# UV_-_SERVO_CTRL.net
KiCad netlist of a schematic drawn in EAGLE
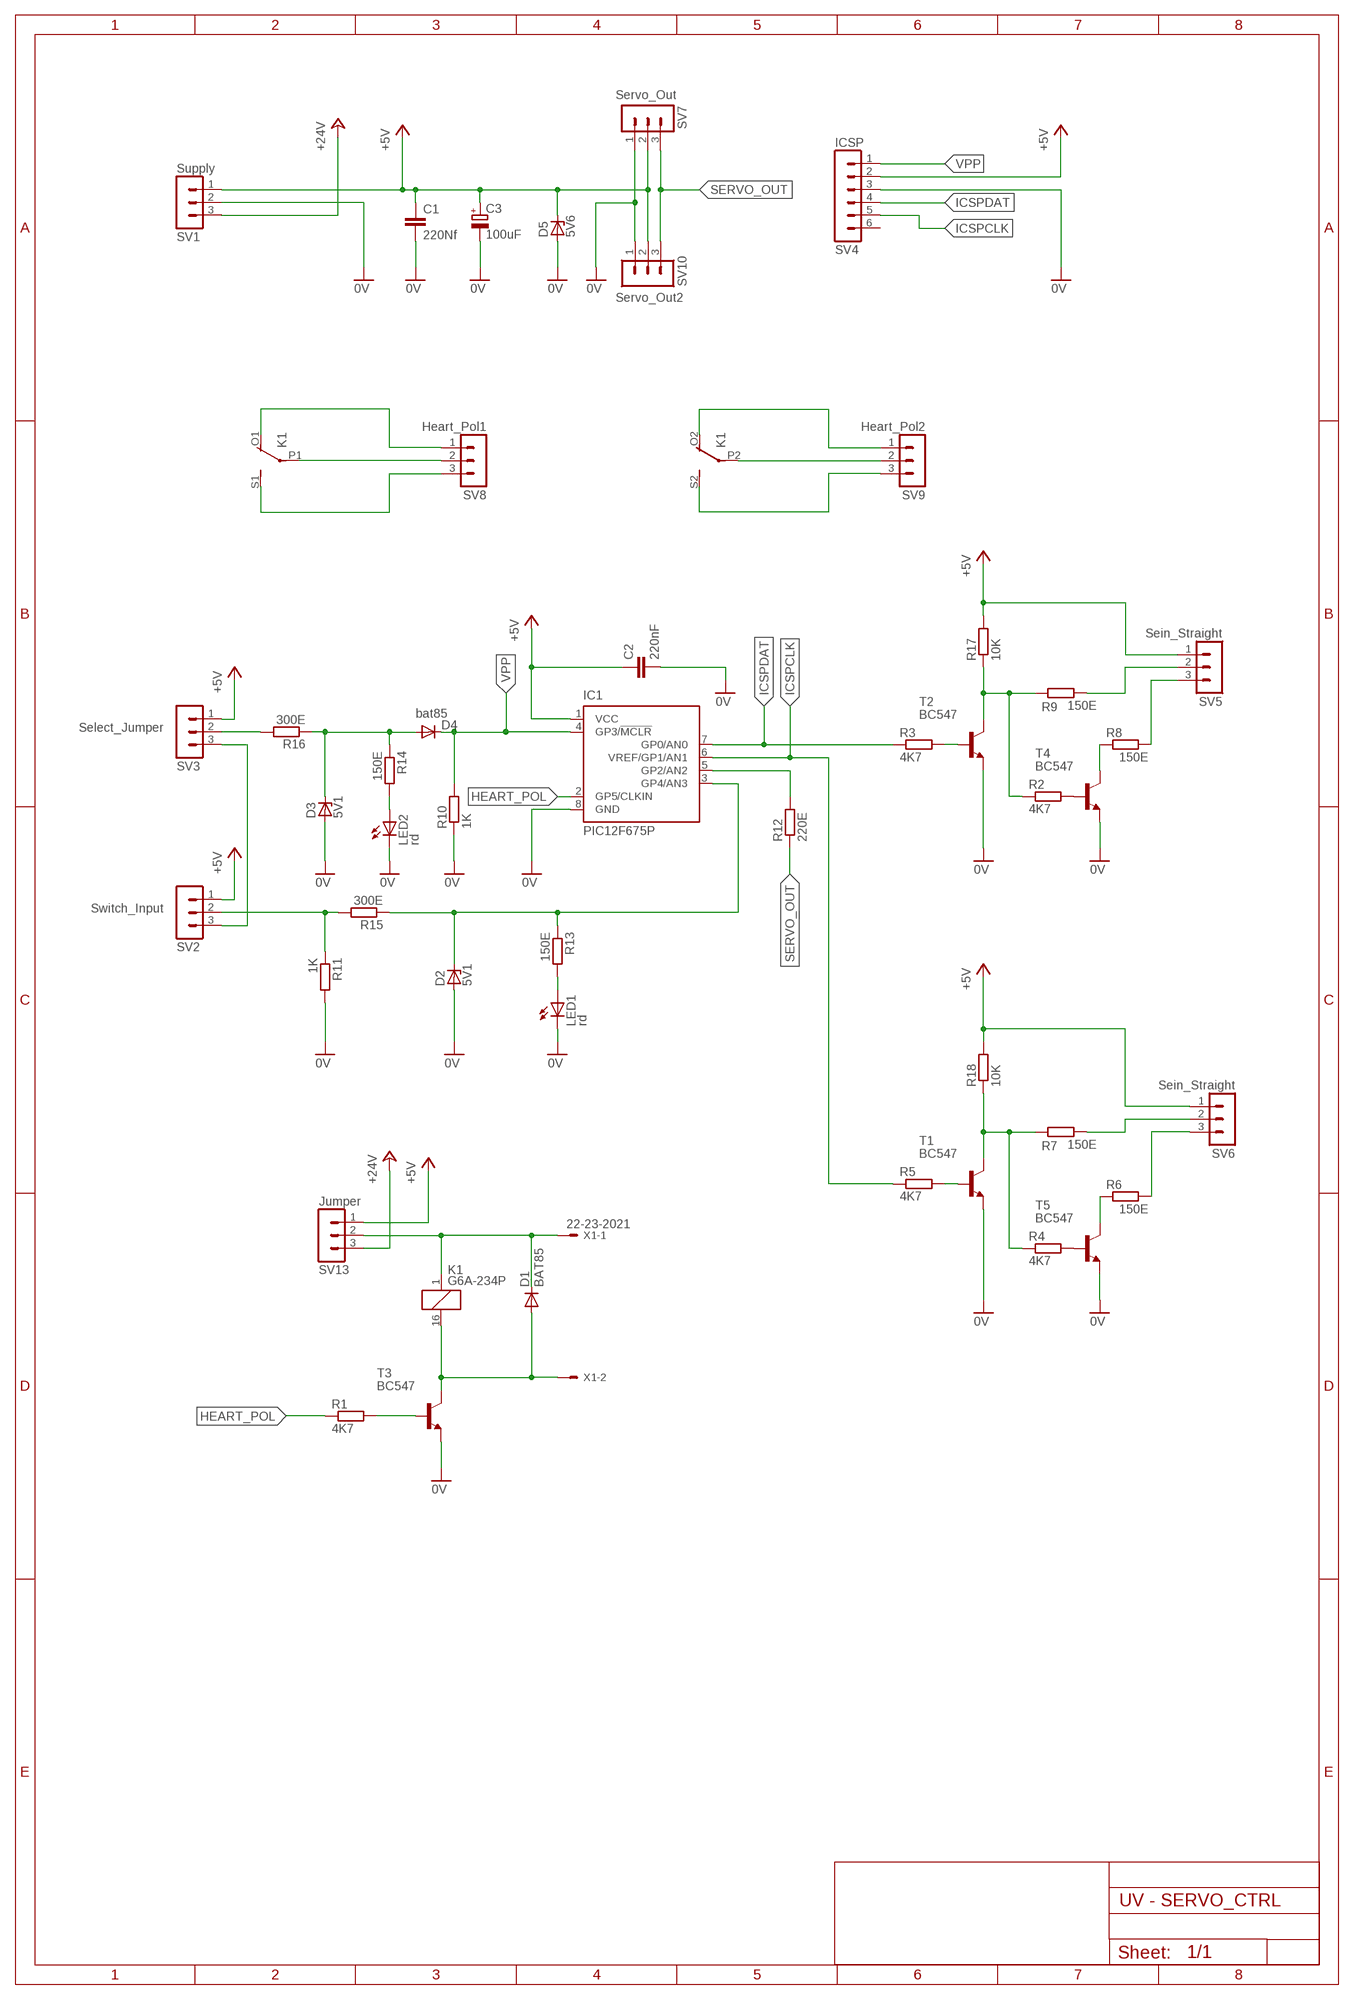
[diagram p0: schematic, sheet 1]

(export (version "E")
  (design (tool "Eeschema 10.0.6"))
  (components
    (comp (ref "C1")
      (value "220Nf")
      (footprint "eagle-import:C050-025X075")
      (fields (field (name "MPN") "MCPBSFC-1J222KA45"))
      (libsource (lib "eagle-import") (part "C-EU050-025X075"))
    )
    (comp (ref "C2")
      (value "220nF")
      (footprint "eagle-import:C050-025X075")
      (fields (field (name "MPN") "MCPBSFC-1J222KA45"))
      (libsource (lib "eagle-import") (part "C-EU050-025X075"))
    )
    (comp (ref "C3")
      (value "100uF")
      (footprint "eagle-import:E2,5-7")
      (fields (field (name "MF") "ILLINOIS CAPACITOR,INC.") (field (name "MPN") "107CKE035M"))
      (libsource (lib "eagle-import") (part "CPOL-EUE2.5-7"))
    )
    (comp (ref "D1")
      (value "BAT85")
      (footprint "eagle-import:DO34-7")
      (fields (field (name "MPN") "BAT85,113"))
      (libsource (lib "eagle-import") (part "BAT81"))
    )
    (comp (ref "D2")
      (value "5V1")
      (footprint "eagle-import:DO34Z7")
      (fields (field (name "MPN") "BZX55C5V1-TAP"))
      (libsource (lib "eagle-import") (part "ZENER-DIODEDO34-7"))
    )
    (comp (ref "D3")
      (value "5V1")
      (footprint "eagle-import:DO34Z7")
      (fields (field (name "MPN") "BZX55C5V1-TAP"))
      (libsource (lib "eagle-import") (part "ZENER-DIODEDO34-7"))
    )
    (comp (ref "D4")
      (value "bat85")
      (footprint "eagle-import:DO34-7")
      (fields (field (name "MPN") "BAT85,113"))
      (libsource (lib "eagle-import") (part "BAT81"))
    )
    (comp (ref "D5")
      (value "5V6")
      (footprint "eagle-import:C1702-15")
      (fields (field (name "MF") "FAIRCHILD SEMICONDUCTOR") (field (name "MPN") "BZX85C5V1"))
      (libsource (lib "eagle-import") (part "1N5333"))
    )
    (comp (ref "IC1")
      (value "PIC12F675P")
      (footprint "eagle-import:DIL8")
      (fields
        (field (name "MF") "MICROCHIP")
        (field (name "MPN") "PIC12F675-E/P")
        (field (name "MF_1") "MICROCHIP")
        (field (name "MPN_1") "PIC12F675-E/P")
        (field (name "OC_NEWARK") "92C4340")
      )
      (libsource (lib "eagle-import") (part "PIC12F675P"))
    )
    (comp (ref "K1")
      (value "G6A-234P")
      (footprint "eagle-import:G6A-234P")
      (fields
        (field (name "MF") "OMRON COMPONENTS USA")
        (field (name "MPN") "G6A-234P-ST40-US-DC12")
        (field (name "OC_NEWARK") "89C6109")
      )
      (libsource (lib "eagle-import") (part "G6A-234P"))
    )
    (comp (ref "LED1")
      (value "rd")
      (footprint "eagle-import:LED3MM")
      (fields (field (name "MPN") "L-934ND"))
      (libsource (lib "eagle-import") (part "LED3MM"))
    )
    (comp (ref "LED2")
      (value "rd")
      (footprint "eagle-import:LED3MM")
      (fields (field (name "MPN") "L-934ND"))
      (libsource (lib "eagle-import") (part "LED3MM"))
    )
    (comp (ref "R1")
      (value "4K7")
      (footprint "eagle-import:0207_2V")
      (fields (field (name "MF") "FARNELL") (field (name "MPN") "MCF 0.25W 4K7"))
      (libsource (lib "eagle-import") (part "R-EU_0207/2V"))
    )
    (comp (ref "R2")
      (value "4K7")
      (footprint "eagle-import:0207_2V")
      (fields (field (name "MF") "FARNELL") (field (name "MPN") "MCF 0.25W 4K7"))
      (libsource (lib "eagle-import") (part "R-EU_0207/2V"))
    )
    (comp (ref "R3")
      (value "4K7")
      (footprint "eagle-import:0207_2V")
      (fields (field (name "MF") "FARNELL") (field (name "MPN") "MCF 0.25W 4K7"))
      (libsource (lib "eagle-import") (part "R-EU_0207/2V"))
    )
    (comp (ref "R4")
      (value "4K7")
      (footprint "eagle-import:0207_2V")
      (fields (field (name "MF") "FARNELL") (field (name "MPN") "MCF 0.25W 4K7"))
      (libsource (lib "eagle-import") (part "R-EU_0207/2V"))
    )
    (comp (ref "R5")
      (value "4K7")
      (footprint "eagle-import:0207_2V")
      (fields (field (name "MF") "FARNELL") (field (name "MPN") "MCF 0.25W 4K7"))
      (libsource (lib "eagle-import") (part "R-EU_0207/2V"))
    )
    (comp (ref "R6")
      (value "150E")
      (footprint "eagle-import:0207_2V")
      (fields (field (name "MF") "FARNELL") (field (name "MPN") "MCF 0.25W 150R"))
      (libsource (lib "eagle-import") (part "R-EU_0207/2V"))
    )
    (comp (ref "R7")
      (value "150E")
      (footprint "eagle-import:0207_2V")
      (fields (field (name "MF") "FARNELL") (field (name "MPN") "MCF 0.25W 150R"))
      (libsource (lib "eagle-import") (part "R-EU_0207/2V"))
    )
    (comp (ref "R8")
      (value "150E")
      (footprint "eagle-import:0207_2V")
      (fields (field (name "MF") "FARNELL") (field (name "MPN") "MCF 0.25W 150R"))
      (libsource (lib "eagle-import") (part "R-EU_0207/2V"))
    )
    (comp (ref "R9")
      (value "150E")
      (footprint "eagle-import:0207_2V")
      (fields (field (name "MF") "FARNELL") (field (name "MPN") "MCF 0.25W 150R"))
      (libsource (lib "eagle-import") (part "R-EU_0207/2V"))
    )
    (comp (ref "R10")
      (value "1K")
      (footprint "eagle-import:0207_2V")
      (fields (field (name "MF") "FARNELL") (field (name "MPN") "MCF 0.25W 1K"))
      (libsource (lib "eagle-import") (part "R-EU_0207/2V"))
    )
    (comp (ref "R11")
      (value "1K")
      (footprint "eagle-import:0207_2V")
      (fields (field (name "MF") "FARNELL") (field (name "MPN") "MCF 0.25W 1K"))
      (libsource (lib "eagle-import") (part "R-EU_0207/2V"))
    )
    (comp (ref "R12")
      (value "220E")
      (footprint "eagle-import:0207_2V")
      (fields (field (name "MF") "FARNELL") (field (name "MPN") "MCF 0.25W 220R"))
      (libsource (lib "eagle-import") (part "R-EU_0207/2V"))
    )
    (comp (ref "R13")
      (value "150E")
      (footprint "eagle-import:0207_2V")
      (fields (field (name "MF") "FARNELL") (field (name "MPN") "MCF 0.25W 150R"))
      (libsource (lib "eagle-import") (part "R-EU_0207/2V"))
    )
    (comp (ref "R14")
      (value "150E")
      (footprint "eagle-import:0207_2V")
      (fields (field (name "MF") "FARNELL") (field (name "MPN") "MCF 0.25W 150R"))
      (libsource (lib "eagle-import") (part "R-EU_0207/2V"))
    )
    (comp (ref "R15")
      (value "300E")
      (footprint "eagle-import:0207_2V")
      (fields (field (name "MF") "FARNELL") (field (name "MPN") "MF25 300R"))
      (libsource (lib "eagle-import") (part "R-EU_0207/2V"))
    )
    (comp (ref "R16")
      (value "300E")
      (footprint "eagle-import:0207_2V")
      (fields (field (name "MF") "FARNELL") (field (name "MPN") "MF25 300R"))
      (libsource (lib "eagle-import") (part "R-EU_0207/2V"))
    )
    (comp (ref "R17")
      (value "10K")
      (footprint "eagle-import:0207_2V")
      (fields (field (name "MF") "FARNELL") (field (name "MPN") "MCF 0.25W 10K"))
      (libsource (lib "eagle-import") (part "R-EU_0207/2V"))
    )
    (comp (ref "R18")
      (value "10K")
      (footprint "eagle-import:0207_2V")
      (fields (field (name "MF") "FARNELL") (field (name "MPN") "MCF 0.25W 10K"))
      (libsource (lib "eagle-import") (part "R-EU_0207/2V"))
    )
    (comp (ref "SV1")
      (value "Supply")
      (footprint "eagle-import:MA03-1")
      (fields (field (name "MPN") "90120-0761") (field (name "OC_NEWARK") "34R6158"))
      (libsource (lib "eagle-import") (part "MA03-1"))
    )
    (comp (ref "SV2")
      (value "Switch_Input")
      (footprint "eagle-import:MA03-1")
      (fields (field (name "MPN") "90120-0761") (field (name "OC_NEWARK") "34R6158"))
      (libsource (lib "eagle-import") (part "MA03-1"))
    )
    (comp (ref "SV3")
      (value "Select_Jumper")
      (footprint "eagle-import:MA03-1")
      (fields (field (name "MPN") "90120-0761") (field (name "OC_NEWARK") "34R6158"))
      (libsource (lib "eagle-import") (part "MA03-1"))
    )
    (comp (ref "SV4")
      (value "ICSP")
      (footprint "eagle-import:MA06-1")
      (fields (field (name "MPN") "90120-0761") (field (name "OC_NEWARK") "34R6158"))
      (libsource (lib "eagle-import") (part "MA06-1"))
    )
    (comp (ref "SV5")
      (value "Sein_Straight")
      (footprint "eagle-import:MA03-1")
      (fields (field (name "MPN") "90120-0761") (field (name "OC_NEWARK") "34R6158"))
      (libsource (lib "eagle-import") (part "MA03-1"))
    )
    (comp (ref "SV6")
      (value "Sein_Straight")
      (footprint "eagle-import:MA03-1")
      (fields
        (field (name "MPN") "90120-0761")
        (field (name "OC_FARNELL") "unknown")
        (field (name "OC_NEWARK") "34R6158")
      )
      (libsource (lib "eagle-import") (part "MA03-1"))
    )
    (comp (ref "SV7")
      (value "Servo_Out")
      (footprint "eagle-import:MA03-1")
      (fields (field (name "MPN") "90120-0761") (field (name "OC_NEWARK") "34R6158"))
      (libsource (lib "eagle-import") (part "MA03-1"))
    )
    (comp (ref "SV8")
      (value "Heart_Pol1")
      (footprint "eagle-import:MA03-1")
      (fields (field (name "MPN") "90120-0761") (field (name "OC_NEWARK") "34R6158"))
      (libsource (lib "eagle-import") (part "MA03-1"))
    )
    (comp (ref "SV9")
      (value "Heart_Pol2")
      (footprint "eagle-import:MA03-1")
      (fields (field (name "MPN") "90120-0761") (field (name "OC_NEWARK") "34R6158"))
      (libsource (lib "eagle-import") (part "MA03-1"))
    )
    (comp (ref "SV10")
      (value "Servo_Out2")
      (footprint "eagle-import:MA03-1")
      (fields
        (field (name "MPN") "90120-0761")
        (field (name "OC_FARNELL") "unknown")
        (field (name "OC_NEWARK") "34R6158")
      )
      (libsource (lib "eagle-import") (part "MA03-1"))
    )
    (comp (ref "SV13")
      (value "Jumper")
      (footprint "eagle-import:MA03-1")
      (fields
        (field (name "MPN") "90120-0761")
        (field (name "OC_FARNELL") "unknown")
        (field (name "OC_NEWARK") "34R6158")
      )
      (libsource (lib "eagle-import") (part "MA03-1"))
    )
    (comp (ref "T1")
      (value "BC547")
      (footprint "eagle-import:TO92")
      (fields (field (name "MPN") "BC547B"))
      (libsource (lib "eagle-import") (part "BC547"))
    )
    (comp (ref "T2")
      (value "BC547")
      (footprint "eagle-import:TO92")
      (fields (field (name "MPN") "BC547B"))
      (libsource (lib "eagle-import") (part "BC547"))
    )
    (comp (ref "T3")
      (value "BC547")
      (footprint "eagle-import:TO92")
      (fields (field (name "MPN") "BC547B"))
      (libsource (lib "eagle-import") (part "BC547"))
    )
    (comp (ref "T4")
      (value "BC547")
      (footprint "eagle-import:TO92")
      (fields (field (name "MPN") "BC547B"))
      (libsource (lib "eagle-import") (part "BC547"))
    )
    (comp (ref "T5")
      (value "BC547")
      (footprint "eagle-import:TO92")
      (fields (field (name "MPN") "BC547B"))
      (libsource (lib "eagle-import") (part "BC547"))
    )
    (comp (ref "X1")
      (value "22-23-2021")
      (footprint "eagle-import:22-23-2021")
      (fields
        (field (name "MF") "MOLEX")
        (field (name "MF_1") "MOLEX")
        (field (name "MPN") "22-23-2021")
        (field (name "OC_NEWARK") "25C3832")
      )
      (libsource (lib "eagle-import") (part "22-23-2021"))
    )
  )
  (nets
    (net (code "1") (name "+5V") (class "Default")
      (node (ref "C1") (pin "1") (pinfunction "1_1") (pintype "passive"))
      (node (ref "C2") (pin "1") (pinfunction "1_1") (pintype "passive"))
      (node (ref "C3") (pin "+") (pinfunction "+_+") (pintype "passive"))
      (node (ref "D5") (pin "C") (pinfunction "C_C") (pintype "passive"))
      (node (ref "IC1") (pin "1") (pinfunction "VCC_1") (pintype "power_in"))
      (node (ref "R17") (pin "2") (pinfunction "2_2") (pintype "passive"))
      (node (ref "R18") (pin "2") (pinfunction "2_2") (pintype "passive"))
      (node (ref "SV1") (pin "1") (pinfunction "1_1") (pintype "passive"))
      (node (ref "SV10") (pin "2") (pinfunction "2_2") (pintype "passive"))
      (node (ref "SV13") (pin "1") (pinfunction "1_1") (pintype "passive"))
      (node (ref "SV2") (pin "1") (pinfunction "1_1") (pintype "passive"))
      (node (ref "SV3") (pin "1") (pinfunction "1_1") (pintype "passive"))
      (node (ref "SV4") (pin "2") (pinfunction "2_2") (pintype "passive"))
      (node (ref "SV5") (pin "1") (pinfunction "1_1") (pintype "passive"))
      (node (ref "SV6") (pin "1") (pinfunction "1_1") (pintype "passive"))
      (node (ref "SV7") (pin "2") (pinfunction "2_2") (pintype "passive"))
    )
    (net (code "2") (name "+24V") (class "Default")
      (node (ref "SV1") (pin "3") (pinfunction "3_3") (pintype "passive"))
      (node (ref "SV13") (pin "3") (pinfunction "3_3") (pintype "passive"))
    )
    (net (code "3") (name "0V") (class "Default")
      (node (ref "C1") (pin "2") (pinfunction "2_2") (pintype "passive"))
      (node (ref "C2") (pin "2") (pinfunction "2_2") (pintype "passive"))
      (node (ref "C3") (pin "-") (pinfunction "-_-") (pintype "passive"))
      (node (ref "D2") (pin "A") (pinfunction "A_A") (pintype "passive"))
      (node (ref "D3") (pin "A") (pinfunction "A_A") (pintype "passive"))
      (node (ref "D5") (pin "A") (pinfunction "A_A") (pintype "passive"))
      (node (ref "IC1") (pin "8") (pinfunction "GND_8") (pintype "power_in"))
      (node (ref "LED1") (pin "K") (pinfunction "C_K") (pintype "passive"))
      (node (ref "LED2") (pin "K") (pinfunction "C_K") (pintype "passive"))
      (node (ref "R10") (pin "1") (pinfunction "1_1") (pintype "passive"))
      (node (ref "R11") (pin "2") (pinfunction "2_2") (pintype "passive"))
      (node (ref "SV1") (pin "2") (pinfunction "2_2") (pintype "passive"))
      (node (ref "SV10") (pin "1") (pinfunction "1_1") (pintype "passive"))
      (node (ref "SV4") (pin "3") (pinfunction "3_3") (pintype "passive"))
      (node (ref "SV7") (pin "1") (pinfunction "1_1") (pintype "passive"))
      (node (ref "T1") (pin "1") (pinfunction "E_1") (pintype "passive"))
      (node (ref "T2") (pin "1") (pinfunction "E_1") (pintype "passive"))
      (node (ref "T3") (pin "1") (pinfunction "E_1") (pintype "passive"))
      (node (ref "T4") (pin "1") (pinfunction "E_1") (pintype "passive"))
      (node (ref "T5") (pin "1") (pinfunction "E_1") (pintype "passive"))
    )
    (net (code "4") (name "HEART_POL") (class "Default")
      (node (ref "IC1") (pin "2") (pinfunction "GP5/CLKIN_2") (pintype "bidirectional"))
      (node (ref "R1") (pin "1") (pinfunction "1_1") (pintype "passive"))
    )
    (net (code "5") (name "ICSPCLK") (class "Default")
      (node (ref "IC1") (pin "6") (pinfunction "VREF/GP1/AN1_6") (pintype "bidirectional"))
      (node (ref "R5") (pin "1") (pinfunction "1_1") (pintype "passive"))
      (node (ref "SV4") (pin "5") (pinfunction "5_5") (pintype "passive"))
    )
    (net (code "6") (name "ICSPDAT") (class "Default")
      (node (ref "IC1") (pin "7") (pinfunction "GP0/AN0_7") (pintype "bidirectional"))
      (node (ref "R3") (pin "1") (pinfunction "1_1") (pintype "passive"))
      (node (ref "SV4") (pin "4") (pinfunction "4_4") (pintype "passive"))
    )
    (net (code "7") (name "Net-(D3-PadC)") (class "Default")
      (node (ref "D3") (pin "C") (pinfunction "C_C") (pintype "passive"))
      (node (ref "D4") (pin "A") (pinfunction "A_A") (pintype "passive"))
      (node (ref "R14") (pin "1") (pinfunction "1_1") (pintype "passive"))
      (node (ref "R16") (pin "1") (pinfunction "1_1") (pintype "passive"))
    )
    (net (code "8") (name "Net-(IC1-GP2{slash}AN2)") (class "Default")
      (node (ref "IC1") (pin "5") (pinfunction "GP2/AN2_5") (pintype "bidirectional"))
      (node (ref "R12") (pin "2") (pinfunction "2_2") (pintype "passive"))
    )
    (net (code "9") (name "Net-(IC1-GP4{slash}AN3)") (class "Default")
      (node (ref "D2") (pin "C") (pinfunction "C_C") (pintype "passive"))
      (node (ref "IC1") (pin "3") (pinfunction "GP4/AN3_3") (pintype "bidirectional"))
      (node (ref "R13") (pin "1") (pinfunction "1_1") (pintype "passive"))
      (node (ref "R15") (pin "1") (pinfunction "1_1") (pintype "passive"))
    )
    (net (code "10") (name "Net-(K1A-2)") (class "Default")
      (node (ref "D1") (pin "A") (pinfunction "A_A") (pintype "passive"))
      (node (ref "K1") (pin "16") (pinfunction "2_16") (pintype "passive"))
      (node (ref "T3") (pin "3") (pinfunction "C_3") (pintype "passive"))
      (node (ref "X1") (pin "2") (pinfunction "S_2") (pintype "passive"))
    )
    (net (code "11") (name "Net-(K1B-O)") (class "Default")
      (node (ref "K1") (pin "O1") (pinfunction "O_O1") (pintype "passive"))
      (node (ref "SV8") (pin "1") (pinfunction "1_1") (pintype "passive"))
    )
    (net (code "12") (name "Net-(K1B-P)") (class "Default")
      (node (ref "K1") (pin "P1") (pinfunction "P_P1") (pintype "passive"))
      (node (ref "SV8") (pin "2") (pinfunction "2_2") (pintype "passive"))
    )
    (net (code "13") (name "Net-(K1B-S)") (class "Default")
      (node (ref "K1") (pin "S1") (pinfunction "S_S1") (pintype "passive"))
      (node (ref "SV8") (pin "3") (pinfunction "3_3") (pintype "passive"))
    )
    (net (code "14") (name "Net-(K1C-O)") (class "Default")
      (node (ref "K1") (pin "O2") (pinfunction "O_O2") (pintype "passive"))
      (node (ref "SV9") (pin "1") (pinfunction "1_1") (pintype "passive"))
    )
    (net (code "15") (name "Net-(K1C-P)") (class "Default")
      (node (ref "K1") (pin "P2") (pinfunction "P_P2") (pintype "passive"))
      (node (ref "SV9") (pin "2") (pinfunction "2_2") (pintype "passive"))
    )
    (net (code "16") (name "Net-(K1C-S)") (class "Default")
      (node (ref "K1") (pin "S2") (pinfunction "S_S2") (pintype "passive"))
      (node (ref "SV9") (pin "3") (pinfunction "3_3") (pintype "passive"))
    )
    (net (code "17") (name "Net-(LED1-PadA)") (class "Default")
      (node (ref "LED1") (pin "A") (pinfunction "A_A") (pintype "passive"))
      (node (ref "R13") (pin "2") (pinfunction "2_2") (pintype "passive"))
    )
    (net (code "18") (name "Net-(LED2-PadA)") (class "Default")
      (node (ref "LED2") (pin "A") (pinfunction "A_A") (pintype "passive"))
      (node (ref "R14") (pin "2") (pinfunction "2_2") (pintype "passive"))
    )
    (net (code "19") (name "Net-(R6-Pad2)") (class "Default")
      (node (ref "R6") (pin "2") (pinfunction "2_2") (pintype "passive"))
      (node (ref "SV6") (pin "3") (pinfunction "3_3") (pintype "passive"))
    )
    (net (code "20") (name "Net-(R7-Pad2)") (class "Default")
      (node (ref "R7") (pin "2") (pinfunction "2_2") (pintype "passive"))
      (node (ref "SV6") (pin "2") (pinfunction "2_2") (pintype "passive"))
    )
    (net (code "21") (name "Net-(R8-Pad2)") (class "Default")
      (node (ref "R8") (pin "2") (pinfunction "2_2") (pintype "passive"))
      (node (ref "SV5") (pin "3") (pinfunction "3_3") (pintype "passive"))
    )
    (net (code "22") (name "Net-(R9-Pad2)") (class "Default")
      (node (ref "R9") (pin "2") (pinfunction "2_2") (pintype "passive"))
      (node (ref "SV5") (pin "2") (pinfunction "2_2") (pintype "passive"))
    )
    (net (code "23") (name "Net-(R11-Pad1)") (class "Default")
      (node (ref "R11") (pin "1") (pinfunction "1_1") (pintype "passive"))
      (node (ref "R15") (pin "2") (pinfunction "2_2") (pintype "passive"))
      (node (ref "SV2") (pin "2") (pinfunction "2_2") (pintype "passive"))
    )
    (net (code "24") (name "Net-(R16-Pad2)") (class "Default")
      (node (ref "R16") (pin "2") (pinfunction "2_2") (pintype "passive"))
      (node (ref "SV3") (pin "2") (pinfunction "2_2") (pintype "passive"))
    )
    (net (code "25") (name "Net-(SV2-Pad3)") (class "Default")
      (node (ref "SV2") (pin "3") (pinfunction "3_3") (pintype "passive"))
      (node (ref "SV3") (pin "3") (pinfunction "3_3") (pintype "passive"))
    )
    (net (code "26") (name "Net-(T1-B)") (class "Default")
      (node (ref "R5") (pin "2") (pinfunction "2_2") (pintype "passive"))
      (node (ref "T1") (pin "2") (pinfunction "B_2") (pintype "passive"))
    )
    (net (code "27") (name "Net-(T1-C)") (class "Default")
      (node (ref "R18") (pin "1") (pinfunction "1_1") (pintype "passive"))
      (node (ref "R4") (pin "1") (pinfunction "1_1") (pintype "passive"))
      (node (ref "R7") (pin "1") (pinfunction "1_1") (pintype "passive"))
      (node (ref "T1") (pin "3") (pinfunction "C_3") (pintype "passive"))
    )
    (net (code "28") (name "Net-(T2-B)") (class "Default")
      (node (ref "R3") (pin "2") (pinfunction "2_2") (pintype "passive"))
      (node (ref "T2") (pin "2") (pinfunction "B_2") (pintype "passive"))
    )
    (net (code "29") (name "Net-(T2-C)") (class "Default")
      (node (ref "R17") (pin "1") (pinfunction "1_1") (pintype "passive"))
      (node (ref "R2") (pin "1") (pinfunction "1_1") (pintype "passive"))
      (node (ref "R9") (pin "1") (pinfunction "1_1") (pintype "passive"))
      (node (ref "T2") (pin "3") (pinfunction "C_3") (pintype "passive"))
    )
    (net (code "30") (name "Net-(T3-B)") (class "Default")
      (node (ref "R1") (pin "2") (pinfunction "2_2") (pintype "passive"))
      (node (ref "T3") (pin "2") (pinfunction "B_2") (pintype "passive"))
    )
    (net (code "31") (name "Net-(T4-B)") (class "Default")
      (node (ref "R2") (pin "2") (pinfunction "2_2") (pintype "passive"))
      (node (ref "T4") (pin "2") (pinfunction "B_2") (pintype "passive"))
    )
    (net (code "32") (name "Net-(T4-C)") (class "Default")
      (node (ref "R8") (pin "1") (pinfunction "1_1") (pintype "passive"))
      (node (ref "T4") (pin "3") (pinfunction "C_3") (pintype "passive"))
    )
    (net (code "33") (name "Net-(T5-B)") (class "Default")
      (node (ref "R4") (pin "2") (pinfunction "2_2") (pintype "passive"))
      (node (ref "T5") (pin "2") (pinfunction "B_2") (pintype "passive"))
    )
    (net (code "34") (name "Net-(T5-C)") (class "Default")
      (node (ref "R6") (pin "1") (pinfunction "1_1") (pintype "passive"))
      (node (ref "T5") (pin "3") (pinfunction "C_3") (pintype "passive"))
    )
    (net (code "35") (name "Net-(X1A-S)") (class "Default")
      (node (ref "D1") (pin "C") (pinfunction "C_C") (pintype "passive"))
      (node (ref "K1") (pin "1") (pinfunction "1_1") (pintype "passive"))
      (node (ref "SV13") (pin "2") (pinfunction "2_2") (pintype "passive"))
      (node (ref "X1") (pin "1") (pinfunction "S_1") (pintype "passive"))
    )
    (net (code "36") (name "SERVO_OUT") (class "Default")
      (node (ref "R12") (pin "1") (pinfunction "1_1") (pintype "passive"))
      (node (ref "SV10") (pin "3") (pinfunction "3_3") (pintype "passive"))
      (node (ref "SV7") (pin "3") (pinfunction "3_3") (pintype "passive"))
    )
    (net (code "37") (name "VPP") (class "Default")
      (node (ref "D4") (pin "C") (pinfunction "C_C") (pintype "passive"))
      (node (ref "IC1") (pin "4") (pinfunction "GP3/~{MCLR}_4") (pintype "input"))
      (node (ref "R10") (pin "2") (pinfunction "2_2") (pintype "passive"))
      (node (ref "SV4") (pin "1") (pinfunction "1_1") (pintype "passive"))
    )
    (net (code "38") (name "unconnected-(SV4-Pad6)") (class "Default")
      (node (ref "SV4") (pin "6") (pinfunction "6_6") (pintype "passive"))
    )
  )
)
